# Sensor.net
KiCad netlist of a schematic drawn in Altium Designer
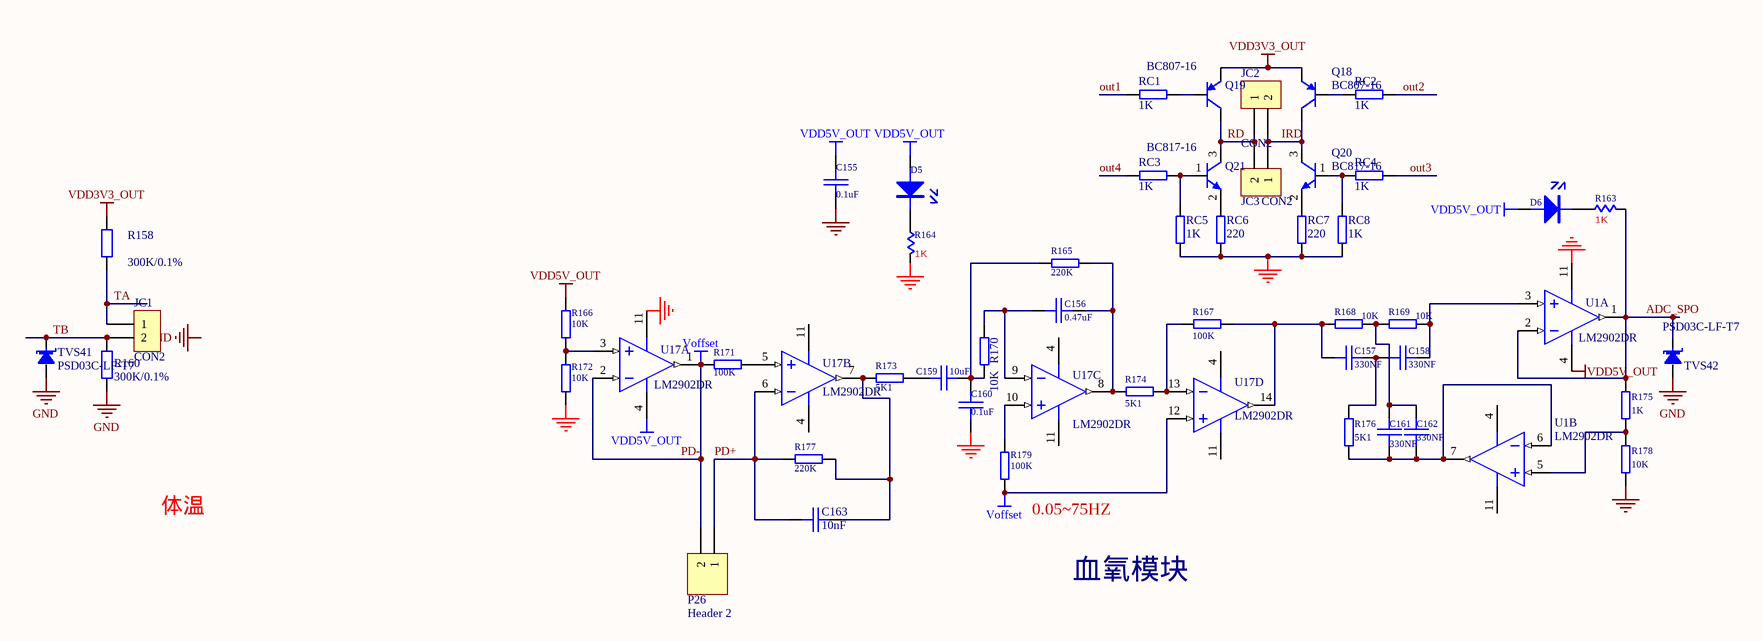
[diagram p0: Sensor.SchDoc]

(export (version "E")
  (design (tool "Eeschema 10.0.6"))
  (components
    (comp (ref "C155")
      (value "0.1uF")
      (footprint "C0603")
      (description "Capacitor")
      (libsource (lib "*") (part "CAP"))
    )
    (comp (ref "C156")
      (value "0.47uF")
      (footprint "C0603")
      (description "Capacitor")
      (libsource (lib "*") (part "CAP"))
    )
    (comp (ref "C157")
      (value "330NF")
      (footprint "C0603")
      (description "Capacitor")
      (libsource (lib "*") (part "CAP"))
    )
    (comp (ref "C158")
      (value "330NF")
      (footprint "C0603")
      (description "Capacitor")
      (libsource (lib "*") (part "CAP"))
    )
    (comp (ref "C159")
      (value "10uF")
      (footprint "C0603")
      (description "Capacitor")
      (libsource (lib "*") (part "CAP"))
    )
    (comp (ref "C160")
      (value "0.1uF")
      (footprint "C0603")
      (description "Capacitor")
      (libsource (lib "*") (part "CAP"))
    )
    (comp (ref "C161")
      (value "330NF")
      (footprint "C0603")
      (description "Capacitor")
      (libsource (lib "*") (part "CAP"))
    )
    (comp (ref "C162")
      (value "330NF")
      (footprint "C0603")
      (description "Capacitor")
      (libsource (lib "*") (part "CAP"))
    )
    (comp (ref "C163")
      (value "10nF")
      (footprint "0603C")
      (description "Capacitor")
      (libsource (lib "*") (part "CAP"))
    )
    (comp (ref "D5")
      (value "LED")
      (footprint "LED0603")
      (description "Diode")
      (libsource (lib "*") (part "DIODE_LED"))
    )
    (comp (ref "D6")
      (value "LED")
      (footprint "LED0603")
      (description "Diode")
      (libsource (lib "*") (part "DIODE_LED"))
    )
    (comp (ref "JC1")
      (value "CON2")
      (footprint "2X2.54MMZ")
      (description "Connector")
      (libsource (lib "") (part "CON2_1"))
    )
    (comp (ref "JC2")
      (value "CON2")
      (footprint "2X2.54MMZ")
      (description "Connector")
      (libsource (lib "*") (part "CON2"))
    )
    (comp (ref "JC3")
      (value "CON2")
      (footprint "2X2.54MMZ")
      (description "Connector")
      (libsource (lib "") (part "CON2_2"))
    )
    (comp (ref "P26")
      (value "Header 2")
      (footprint "2X2.54MMZ")
      (description "Header, 2-Pin")
      (fields (field (name "PUBLISHER") "Altium Limited"))
      (libsource (lib "Miscellaneous Connectors") (part "Header 2"))
    )
    (comp (ref "Q18")
      (value "BC807-16")
      (footprint "SOT-23")
      (description "PNP")
      (libsource (lib "XiaoyI") (part "PNP"))
    )
    (comp (ref "Q19")
      (value "BC807-16")
      (footprint "SOT-23")
      (description "PNP")
      (libsource (lib "XiaoyI") (part "PNP"))
    )
    (comp (ref "Q20")
      (value "BC817-16")
      (footprint "SOT-23")
      (description "三极管")
      (libsource (lib "XiaoyI") (part "NPN-1"))
    )
    (comp (ref "Q21")
      (value "BC817-16")
      (footprint "SOT-23")
      (description "三极管")
      (libsource (lib "XiaoyI") (part "NPN-1"))
    )
    (comp (ref "R158")
      (value "300K/0.1%")
      (footprint "SMD-0603")
      (description "贴片电阻 1%")
      (libsource (lib "XiaoyI") (part "RES2"))
    )
    (comp (ref "R160")
      (value "300K/0.1%")
      (footprint "SMD-0603")
      (description "贴片电阻 1%")
      (libsource (lib "XiaoyI") (part "RES2"))
    )
    (comp (ref "R163") (value "1K") (footprint "0603R") (libsource (lib "*") (part "RES-SMD")))
    (comp (ref "R164") (value "1K") (footprint "0603R") (libsource (lib "*") (part "RES-SMD")))
    (comp (ref "R165") (value "220K") (footprint "0603R") (libsource (lib "*") (part "RES2")))
    (comp (ref "R166") (value "10K") (footprint "0603R") (libsource (lib "*") (part "RES2")))
    (comp (ref "R167") (value "100K") (footprint "0603R") (libsource (lib "*") (part "RES2")))
    (comp (ref "R168") (value "10K") (footprint "0603R") (libsource (lib "*") (part "RES2")))
    (comp (ref "R169") (value "10K") (footprint "0603R") (libsource (lib "*") (part "RES2")))
    (comp (ref "R170") (value "10K") (footprint "0603R") (libsource (lib "*") (part "RES2")))
    (comp (ref "R171") (value "100K") (footprint "0603R") (libsource (lib "*") (part "RES2")))
    (comp (ref "R172") (value "10K") (footprint "0603R") (libsource (lib "*") (part "RES2")))
    (comp (ref "R173") (value "5K1") (footprint "0603R") (libsource (lib "*") (part "RES2")))
    (comp (ref "R174") (value "5K1") (footprint "0603R") (libsource (lib "*") (part "RES2")))
    (comp (ref "R175") (value "1K") (footprint "0603R") (libsource (lib "*") (part "RES2")))
    (comp (ref "R176") (value "5K1") (footprint "0603R") (libsource (lib "*") (part "RES2")))
    (comp (ref "R177") (value "220K") (footprint "0603R") (libsource (lib "*") (part "RES2")))
    (comp (ref "R178") (value "10K") (footprint "0603R") (libsource (lib "*") (part "RES2")))
    (comp (ref "R179") (value "100K") (footprint "0603R") (libsource (lib "*") (part "RES2")))
    (comp (ref "RC1") (value "1K") (footprint "0603R") (libsource (lib "*") (part "RES2")))
    (comp (ref "RC2") (value "1K") (footprint "0603R") (libsource (lib "*") (part "RES2")))
    (comp (ref "RC3") (value "1K") (footprint "0603R") (libsource (lib "*") (part "RES2")))
    (comp (ref "RC4") (value "1K") (footprint "0603R") (libsource (lib "*") (part "RES2")))
    (comp (ref "RC5") (value "1K") (footprint "0603R") (libsource (lib "*") (part "RES2")))
    (comp (ref "RC6") (value "220") (footprint "0603R") (libsource (lib "*") (part "RES2")))
    (comp (ref "RC7") (value "220") (footprint "0603R") (libsource (lib "*") (part "RES2")))
    (comp (ref "RC8") (value "1K") (footprint "0603R") (libsource (lib "*") (part "RES2")))
    (comp (ref "TVS41")
      (value "PSD03C-LF-T7")
      (footprint "SOD-323")
      (description "单向TVS")
      (libsource (lib "XiaoyI") (part "TVS-S"))
    )
    (comp (ref "TVS42")
      (value "PSD03C-LF-T7")
      (footprint "SOD-323")
      (description "单向TVS")
      (libsource (lib "XiaoyI") (part "TVS-S"))
    )
    (comp (ref "U1")
      (value "LM2902DR")
      (footprint "SO-14Z")
      (description "Low Power Quad Operational Amplifier")
      (libsource (lib "*") (part "TLC274"))
    )
    (comp (ref "U17")
      (value "LM2902DR")
      (footprint "SO-14Z")
      (description "Low Power Quad Operational Amplifier")
      (libsource (lib "*") (part "TLC274"))
    )
  )
  (nets
    (net (code "1") (name "/ADC_SPO") (class "Default")
      (node (ref "R163") (pin "2") (pinfunction "2_2") (pintype "passive"))
      (node (ref "R175") (pin "1") (pinfunction "1_1") (pintype "passive"))
      (node (ref "TVS42") (pin "2") (pinfunction "B_2") (pintype "passive"))
      (node (ref "U1") (pin "1") (pinfunction "1_OUT_1") (pintype "output"))
      (node (ref "U1") (pin "2") (pinfunction "1_IN-_2") (pintype "input"))
    )
    (net (code "2") (name "/IRD") (class "Default")
      (node (ref "JC2") (pin "2") (pinfunction "2_2") (pintype "passive"))
      (node (ref "JC3") (pin "1") (pinfunction "1_1") (pintype "passive"))
      (node (ref "Q18") (pin "3") (pinfunction "C_3") (pintype "passive"))
      (node (ref "Q20") (pin "3") (pinfunction "C_3") (pintype "passive"))
    )
    (net (code "3") (name "/PD+") (class "Default")
      (node (ref "C163") (pin "2") (pinfunction "2_2") (pintype "passive"))
      (node (ref "P26") (pin "1") (pinfunction "1_1") (pintype "passive"))
      (node (ref "R177") (pin "2") (pinfunction "2_2") (pintype "passive"))
      (node (ref "U17") (pin "6") (pinfunction "2_IN-_6") (pintype "input"))
    )
    (net (code "4") (name "/RD") (class "Default")
      (node (ref "JC2") (pin "1") (pinfunction "1_1") (pintype "passive"))
      (node (ref "JC3") (pin "2") (pinfunction "2_2") (pintype "passive"))
      (node (ref "Q19") (pin "3") (pinfunction "C_3") (pintype "passive"))
      (node (ref "Q21") (pin "3") (pinfunction "C_3") (pintype "passive"))
    )
    (net (code "5") (name "/TA") (class "Default")
      (node (ref "JC1") (pin "1") (pinfunction "1_1") (pintype "passive"))
      (node (ref "R158") (pin "1") (pinfunction "1_1") (pintype "passive"))
    )
    (net (code "6") (name "/TB") (class "Default")
      (node (ref "JC1") (pin "2") (pinfunction "2_2") (pintype "passive"))
      (node (ref "R160") (pin "2") (pinfunction "2_2") (pintype "passive"))
      (node (ref "TVS41") (pin "2") (pinfunction "B_2") (pintype "passive"))
    )
    (net (code "7") (name "/out1") (class "Default")
      (node (ref "RC1") (pin "2") (pinfunction "2_2") (pintype "passive"))
    )
    (net (code "8") (name "/out2") (class "Default")
      (node (ref "RC2") (pin "2") (pinfunction "2_2") (pintype "passive"))
    )
    (net (code "9") (name "/out3") (class "Default")
      (node (ref "RC4") (pin "2") (pinfunction "2_2") (pintype "passive"))
    )
    (net (code "10") (name "/out4") (class "Default")
      (node (ref "RC3") (pin "2") (pinfunction "2_2") (pintype "passive"))
    )
    (net (code "11") (name "GND") (class "Default")
      (node (ref "C155") (pin "1") (pinfunction "1_1") (pintype "passive"))
      (node (ref "C160") (pin "2") (pinfunction "2_2") (pintype "passive"))
      (node (ref "R160") (pin "1") (pinfunction "1_1") (pintype "passive"))
      (node (ref "R164") (pin "2") (pinfunction "2_2") (pintype "passive"))
      (node (ref "R172") (pin "1") (pinfunction "1_1") (pintype "passive"))
      (node (ref "R178") (pin "2") (pinfunction "2_2") (pintype "passive"))
      (node (ref "RC5") (pin "1") (pinfunction "1_1") (pintype "passive"))
      (node (ref "RC6") (pin "2") (pinfunction "2_2") (pintype "passive"))
      (node (ref "RC7") (pin "2") (pinfunction "2_2") (pintype "passive"))
      (node (ref "RC8") (pin "1") (pinfunction "1_1") (pintype "passive"))
      (node (ref "TVS41") (pin "1") (pinfunction "A_1") (pintype "passive"))
      (node (ref "TVS42") (pin "1") (pinfunction "A_1") (pintype "passive"))
      (node (ref "U1") (pin "11") (pinfunction "VEE_11") (pintype "power_in"))
      (node (ref "U17") (pin "11") (pinfunction "VEE_11") (pintype "power_in"))
    )
    (net (code "12") (name "Net-(C157-Pad2)") (class "Default")
      (node (ref "C157") (pin "2") (pinfunction "2_2") (pintype "passive"))
      (node (ref "C158") (pin "1") (pinfunction "1_1") (pintype "passive"))
      (node (ref "R176") (pin "1") (pinfunction "1_1") (pintype "passive"))
    )
    (net (code "13") (name "Net-(C159-Pad1)") (class "Default")
      (node (ref "C159") (pin "1") (pinfunction "1_1") (pintype "passive"))
      (node (ref "C160") (pin "1") (pinfunction "1_1") (pintype "passive"))
      (node (ref "R165") (pin "1") (pinfunction "1_1") (pintype "passive"))
      (node (ref "R170") (pin "1") (pinfunction "1_1") (pintype "passive"))
    )
    (net (code "14") (name "Net-(C159-Pad2)") (class "Default")
      (node (ref "C159") (pin "2") (pinfunction "2_2") (pintype "passive"))
      (node (ref "R173") (pin "1") (pinfunction "1_1") (pintype "passive"))
    )
    (net (code "15") (name "Net-(C161-Pad2)") (class "Default")
      (node (ref "C161") (pin "2") (pinfunction "2_2") (pintype "passive"))
      (node (ref "C162") (pin "2") (pinfunction "2_2") (pintype "passive"))
      (node (ref "R168") (pin "2") (pinfunction "2_2") (pintype "passive"))
      (node (ref "R169") (pin "1") (pinfunction "1_1") (pintype "passive"))
    )
    (net (code "16") (name "Net-(D5-K)") (class "Default")
      (node (ref "D5") (pin "2") (pinfunction "K_2") (pintype "passive"))
      (node (ref "R164") (pin "1") (pinfunction "1_1") (pintype "passive"))
    )
    (net (code "17") (name "Net-(D6-K)") (class "Default")
      (node (ref "D6") (pin "2") (pinfunction "K_2") (pintype "passive"))
      (node (ref "R163") (pin "1") (pinfunction "1_1") (pintype "passive"))
    )
    (net (code "18") (name "Net-(Q18-B)") (class "Default")
      (node (ref "Q18") (pin "1") (pinfunction "B_1") (pintype "passive"))
      (node (ref "RC2") (pin "1") (pinfunction "1_1") (pintype "passive"))
    )
    (net (code "19") (name "Net-(Q19-B)") (class "Default")
      (node (ref "Q19") (pin "1") (pinfunction "B_1") (pintype "passive"))
      (node (ref "RC1") (pin "1") (pinfunction "1_1") (pintype "passive"))
    )
    (net (code "20") (name "Net-(Q20-B)") (class "Default")
      (node (ref "Q20") (pin "1") (pinfunction "B_1") (pintype "passive"))
      (node (ref "RC4") (pin "1") (pinfunction "1_1") (pintype "passive"))
      (node (ref "RC8") (pin "2") (pinfunction "2_2") (pintype "passive"))
    )
    (net (code "21") (name "Net-(Q20-E)") (class "Default")
      (node (ref "Q20") (pin "2") (pinfunction "E_2") (pintype "passive"))
      (node (ref "RC7") (pin "1") (pinfunction "1_1") (pintype "passive"))
    )
    (net (code "22") (name "Net-(Q21-B)") (class "Default")
      (node (ref "Q21") (pin "1") (pinfunction "B_1") (pintype "passive"))
      (node (ref "RC3") (pin "1") (pinfunction "1_1") (pintype "passive"))
      (node (ref "RC5") (pin "2") (pinfunction "2_2") (pintype "passive"))
    )
    (net (code "23") (name "Net-(Q21-E)") (class "Default")
      (node (ref "Q21") (pin "2") (pinfunction "E_2") (pintype "passive"))
      (node (ref "RC6") (pin "1") (pinfunction "1_1") (pintype "passive"))
    )
    (net (code "24") (name "Net-(U1A-1_IN+)") (class "Default")
      (node (ref "C158") (pin "2") (pinfunction "2_2") (pintype "passive"))
      (node (ref "R169") (pin "2") (pinfunction "2_2") (pintype "passive"))
      (node (ref "U1") (pin "3") (pinfunction "1_IN+_3") (pintype "input"))
    )
    (net (code "25") (name "Net-(U1B-2_IN+)") (class "Default")
      (node (ref "R175") (pin "2") (pinfunction "2_2") (pintype "passive"))
      (node (ref "R178") (pin "1") (pinfunction "1_1") (pintype "passive"))
      (node (ref "U1") (pin "5") (pinfunction "2_IN+_5") (pintype "input"))
    )
    (net (code "26") (name "Net-(U1B-2_IN-)") (class "Default")
      (node (ref "C161") (pin "1") (pinfunction "1_1") (pintype "passive"))
      (node (ref "C162") (pin "1") (pinfunction "1_1") (pintype "passive"))
      (node (ref "R176") (pin "2") (pinfunction "2_2") (pintype "passive"))
      (node (ref "U1") (pin "6") (pinfunction "2_IN-_6") (pintype "input"))
      (node (ref "U1") (pin "7") (pinfunction "2_OUT_7") (pintype "output"))
    )
    (net (code "27") (name "Net-(U17A-1_IN+)") (class "Default")
      (node (ref "R166") (pin "1") (pinfunction "1_1") (pintype "passive"))
      (node (ref "R172") (pin "2") (pinfunction "2_2") (pintype "passive"))
      (node (ref "U17") (pin "3") (pinfunction "1_IN+_3") (pintype "input"))
    )
    (net (code "28") (name "Net-(U17B-2_IN+)") (class "Default")
      (node (ref "R171") (pin "2") (pinfunction "2_2") (pintype "passive"))
      (node (ref "U17") (pin "5") (pinfunction "2_IN+_5") (pintype "input"))
    )
    (net (code "29") (name "Net-(U17B-2_OUT)") (class "Default")
      (node (ref "C163") (pin "1") (pinfunction "1_1") (pintype "passive"))
      (node (ref "R173") (pin "2") (pinfunction "2_2") (pintype "passive"))
      (node (ref "R177") (pin "1") (pinfunction "1_1") (pintype "passive"))
      (node (ref "U17") (pin "7") (pinfunction "2_OUT_7") (pintype "output"))
    )
    (net (code "30") (name "Net-(U17C-3_IN+)") (class "Default")
      (node (ref "R179") (pin "2") (pinfunction "2_2") (pintype "passive"))
      (node (ref "U17") (pin "10") (pinfunction "3_IN+_10") (pintype "input"))
    )
    (net (code "31") (name "Net-(U17C-3_IN-)") (class "Default")
      (node (ref "C156") (pin "2") (pinfunction "2_2") (pintype "passive"))
      (node (ref "R170") (pin "2") (pinfunction "2_2") (pintype "passive"))
      (node (ref "U17") (pin "9") (pinfunction "3_IN-_9") (pintype "input"))
    )
    (net (code "32") (name "Net-(U17C-3_OUT)") (class "Default")
      (node (ref "C156") (pin "1") (pinfunction "1_1") (pintype "passive"))
      (node (ref "R165") (pin "2") (pinfunction "2_2") (pintype "passive"))
      (node (ref "R174") (pin "1") (pinfunction "1_1") (pintype "passive"))
      (node (ref "U17") (pin "8") (pinfunction "3_OUT_8") (pintype "output"))
    )
    (net (code "33") (name "Net-(U17D-4_IN-)") (class "Default")
      (node (ref "R167") (pin "1") (pinfunction "1_1") (pintype "passive"))
      (node (ref "R174") (pin "2") (pinfunction "2_2") (pintype "passive"))
      (node (ref "U17") (pin "13") (pinfunction "4_IN-_13") (pintype "input"))
    )
    (net (code "34") (name "Net-(U17D-4_OUT)") (class "Default")
      (node (ref "C157") (pin "1") (pinfunction "1_1") (pintype "passive"))
      (node (ref "R167") (pin "2") (pinfunction "2_2") (pintype "passive"))
      (node (ref "R168") (pin "1") (pinfunction "1_1") (pintype "passive"))
      (node (ref "U17") (pin "14") (pinfunction "4_OUT_14") (pintype "output"))
    )
    (net (code "35") (name "VDD3V3_OUT") (class "Default")
      (node (ref "Q18") (pin "2") (pinfunction "E_2") (pintype "passive"))
      (node (ref "Q19") (pin "2") (pinfunction "E_2") (pintype "passive"))
      (node (ref "R158") (pin "2") (pinfunction "2_2") (pintype "passive"))
    )
    (net (code "36") (name "VDD5V_OUT") (class "Default")
      (node (ref "C155") (pin "2") (pinfunction "2_2") (pintype "passive"))
      (node (ref "D5") (pin "1") (pinfunction "A_1") (pintype "passive"))
      (node (ref "D6") (pin "1") (pinfunction "A_1") (pintype "passive"))
      (node (ref "R166") (pin "2") (pinfunction "2_2") (pintype "passive"))
      (node (ref "U1") (pin "4") (pinfunction "VCC_4") (pintype "power_in"))
      (node (ref "U17") (pin "4") (pinfunction "VCC_4") (pintype "power_in"))
    )
    (net (code "37") (name "Voffset") (class "Default")
      (node (ref "P26") (pin "2") (pinfunction "2_2") (pintype "passive"))
      (node (ref "R171") (pin "1") (pinfunction "1_1") (pintype "passive"))
      (node (ref "R179") (pin "1") (pinfunction "1_1") (pintype "passive"))
      (node (ref "U17") (pin "1") (pinfunction "1_OUT_1") (pintype "output"))
      (node (ref "U17") (pin "12") (pinfunction "4_IN+_12") (pintype "input"))
      (node (ref "U17") (pin "2") (pinfunction "1_IN-_2") (pintype "input"))
    )
    (net (code "38") (name "unconnected-(U1B-VCC-Pad4)") (class "Default")
      (node (ref "U1") (pin "4") (pinfunction "VCC_4") (pintype "power_in"))
    )
    (net (code "39") (name "unconnected-(U1B-VEE-Pad11)") (class "Default")
      (node (ref "U1") (pin "11") (pinfunction "VEE_11") (pintype "power_in"))
    )
    (net (code "40") (name "unconnected-(U17B-VCC-Pad4)") (class "Default")
      (node (ref "U17") (pin "4") (pinfunction "VCC_4") (pintype "power_in"))
    )
    (net (code "41") (name "unconnected-(U17B-VEE-Pad11)") (class "Default")
      (node (ref "U17") (pin "11") (pinfunction "VEE_11") (pintype "power_in"))
    )
    (net (code "42") (name "unconnected-(U17C-VCC-Pad4)") (class "Default")
      (node (ref "U17") (pin "4") (pinfunction "VCC_4") (pintype "power_in"))
    )
    (net (code "43") (name "unconnected-(U17C-VEE-Pad11)") (class "Default")
      (node (ref "U17") (pin "11") (pinfunction "VEE_11") (pintype "power_in"))
    )
    (net (code "44") (name "unconnected-(U17D-VCC-Pad4)") (class "Default")
      (node (ref "U17") (pin "4") (pinfunction "VCC_4") (pintype "power_in"))
    )
    (net (code "45") (name "unconnected-(U17D-VEE-Pad11)") (class "Default")
      (node (ref "U17") (pin "11") (pinfunction "VEE_11") (pintype "power_in"))
    )
  )
)
